# STLink_V3E_SWD.net
KiCad netlist of a schematic drawn in Altium Designer
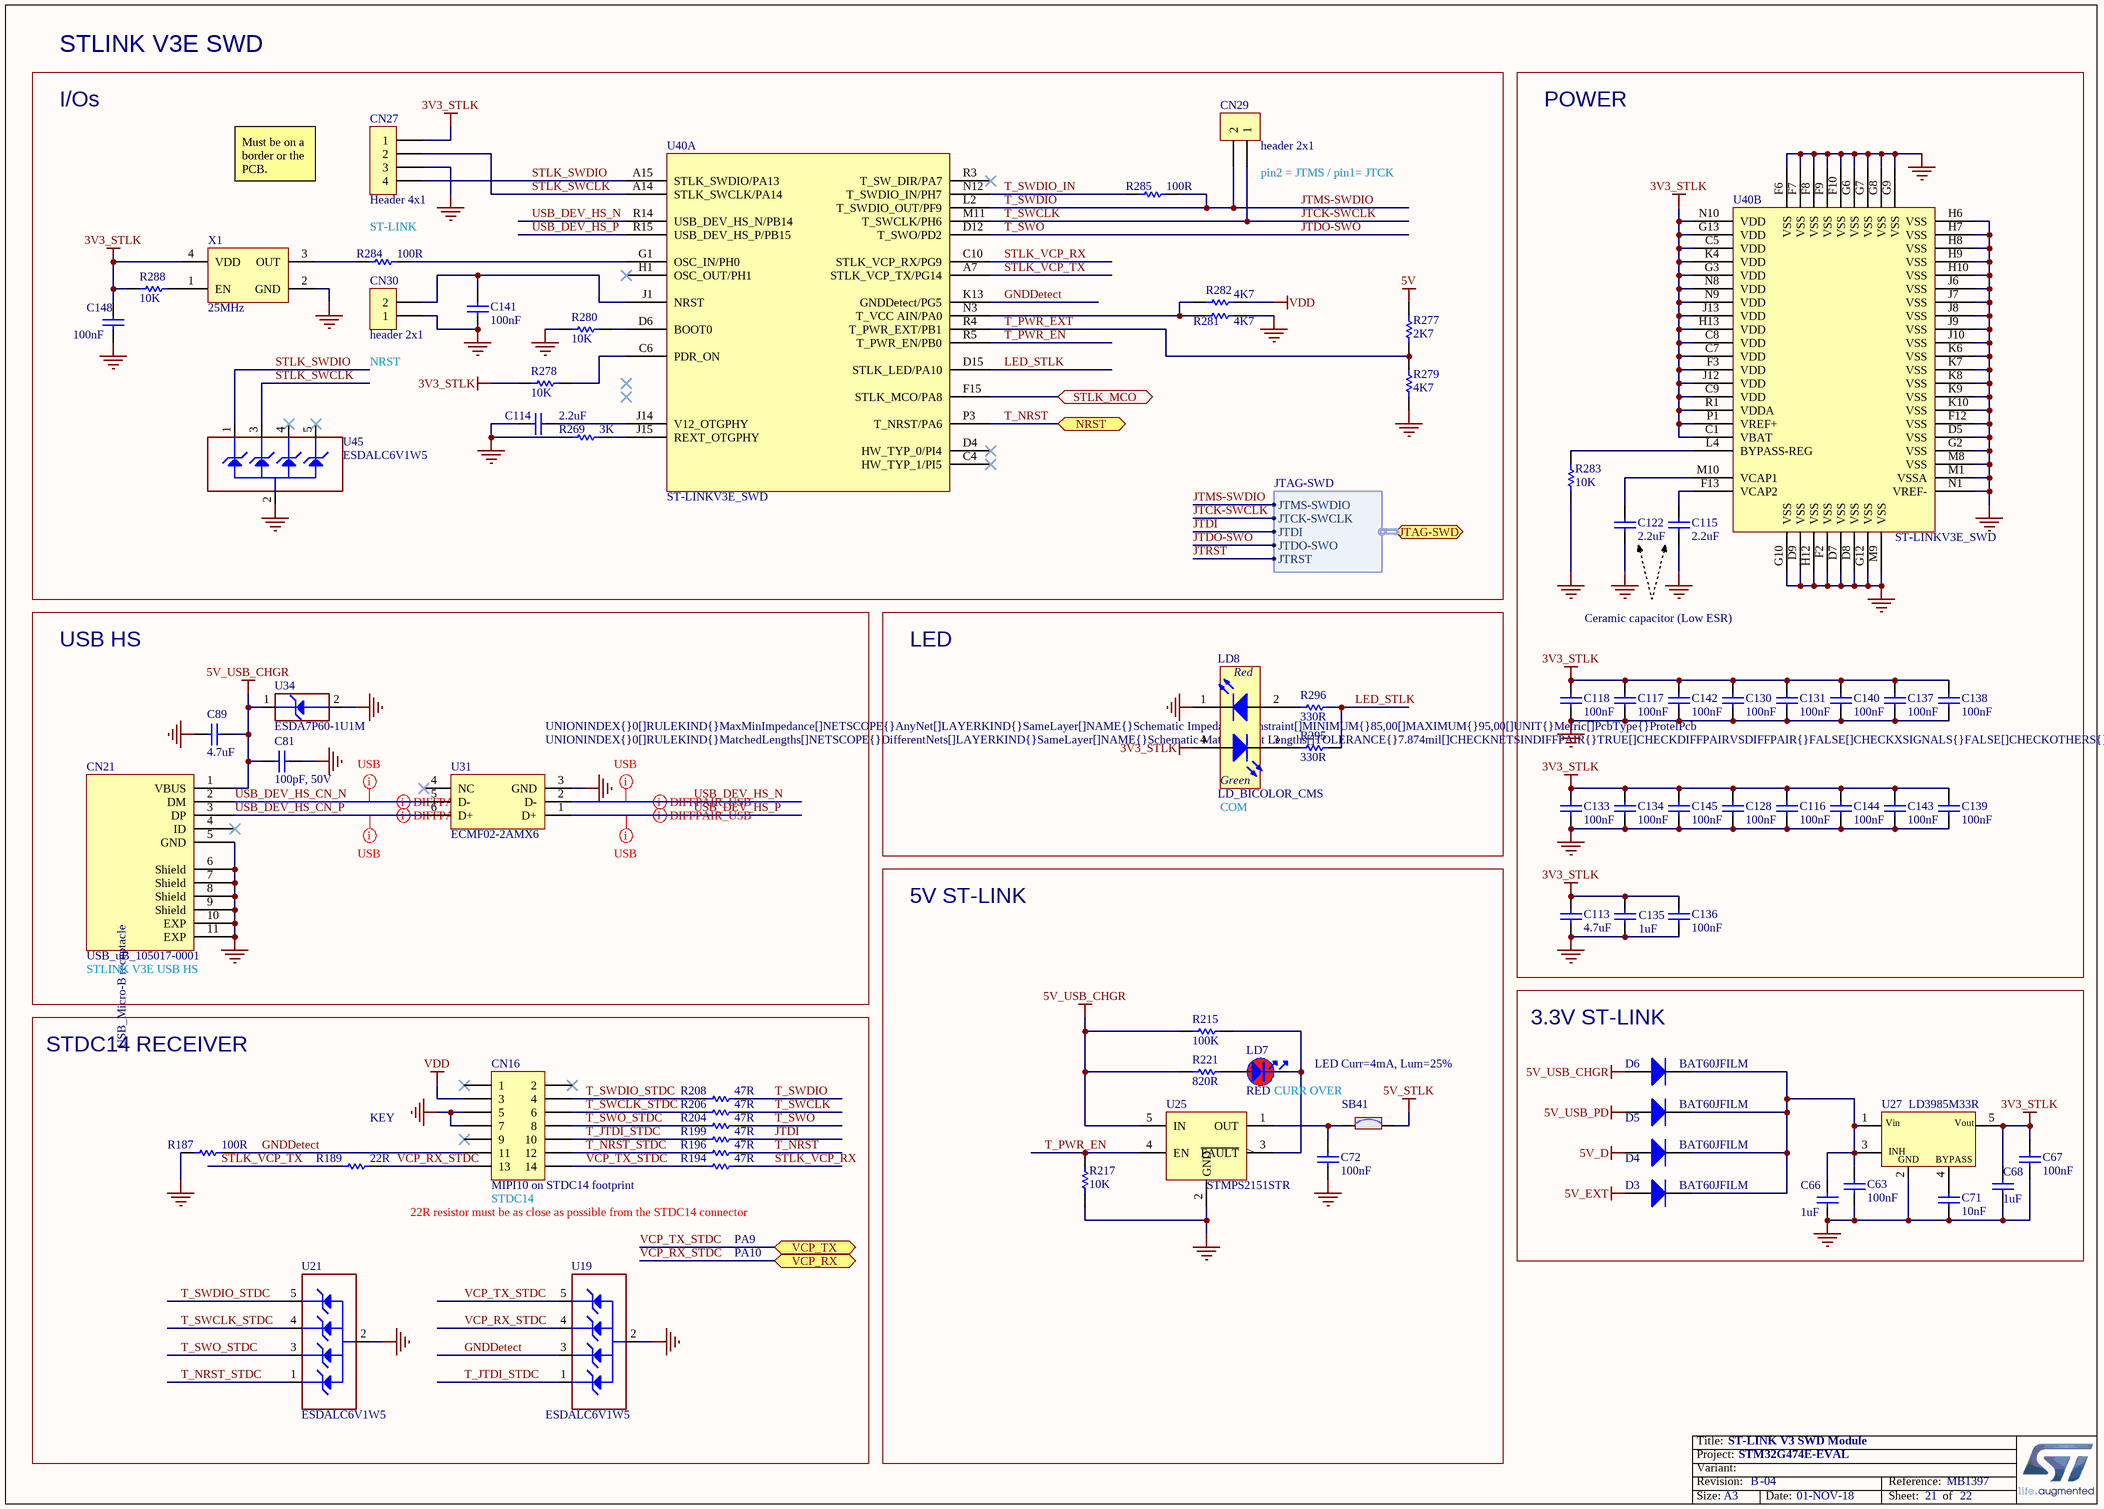
[diagram p0: STLink_V3E_SWD.SchDoc]

(export (version "E")
  (design (tool "Eeschema 10.0.6"))
  (components
    (comp (ref "C63")
      (value "100nF")
      (footprint "C0402")
      (description "Capacitor, MLCC, 100nF, 16V, X7R, 10%, 0402, T=0.5mm")
      (fields
        (field (name "INTERNAL_PART_NUMBER") "MCD-00006")
        (field (name "MANUFACTURER_PART_NUMBER") "CC0402KRX7R7BB104")
      )
      (libsource (lib "MCD_PARTS_database") (part "Capacitor"))
    )
    (comp (ref "C66")
      (value "1uF")
      (footprint "C0603")
      (description "Capacitor, MLCC, 1uF, 16V, X5R, 10%, 0603, T=0,8mm")
      (fields
        (field (name "INTERNAL_PART_NUMBER") "MCD-00010")
        (field (name "MANUFACTURER_PART_NUMBER") "CC0603KRX5R7BB105")
      )
      (libsource (lib "MCD_PARTS_database") (part "Capacitor"))
    )
    (comp (ref "C67")
      (value "100nF")
      (footprint "C0603")
      (description "Capacitor, MLCC, 100nF, 16V, X7R, 10%, 0603, T=0,8mm")
      (fields
        (field (name "INTERNAL_PART_NUMBER") "MCD-00211")
        (field (name "MANUFACTURER_PART_NUMBER") "CC0603KRX7R7BB104")
      )
      (libsource (lib "MCD_PARTS_database") (part "Capacitor"))
    )
    (comp (ref "C68")
      (value "1uF")
      (footprint "C0603")
      (description "Capacitor, MLCC, 1uF, 16V, X5R, 10%, 0603, T=0,8mm")
      (fields
        (field (name "INTERNAL_PART_NUMBER") "MCD-00010")
        (field (name "MANUFACTURER_PART_NUMBER") "CC0603KRX5R7BB105")
      )
      (libsource (lib "MCD_PARTS_database") (part "Capacitor"))
    )
    (comp (ref "C71")
      (value "10nF")
      (footprint "C0402")
      (description "Capacitor, MLCC, 10nF, 16V, X7R, 10%, 0402, T=0.5mm")
      (fields
        (field (name "INTERNAL_PART_NUMBER") "MCD-00011")
        (field (name "MANUFACTURER_PART_NUMBER") "CC0402KRX7R7BB103")
      )
      (libsource (lib "MCD_PARTS_database") (part "Capacitor"))
    )
    (comp (ref "C72")
      (value "100nF")
      (footprint "C0402")
      (description "Capacitor, MLCC, 100nF, 16V, X7R, 10%, 0402, T=0.5mm")
      (fields
        (field (name "INTERNAL_PART_NUMBER") "MCD-00006")
        (field (name "MANUFACTURER_PART_NUMBER") "CC0402KRX7R7BB104")
      )
      (libsource (lib "MCD_PARTS_database") (part "Capacitor"))
    )
    (comp (ref "C81")
      (value "100pF, 50V")
      (footprint "C0603")
      (description "Capacitor,100pF,50V,X7R,10%,0603")
      (fields
        (field (name "INTERNAL_PART_NUMBER") "MCD-01101")
        (field (name "MANUFACTURER_PART_NUMBER") "06035C101JAT4A")
      )
      (libsource (lib "MCD_PARTS_database") (part "Capacitor"))
    )
    (comp (ref "C89")
      (value "4.7uF")
      (footprint "C0603")
      (description "Capacitor, MLCC, 4.7uF, 16V, X5R, 10%, 0603, T=0.8mm")
      (fields
        (field (name "INTERNAL_PART_NUMBER") "MCD-00009")
        (field (name "MANUFACTURER_PART_NUMBER") "CC0603KRX5R7BB475")
      )
      (libsource (lib "MCD_PARTS_database") (part "Capacitor"))
    )
    (comp (ref "C113")
      (value "4.7uF")
      (footprint "C0603")
      (description "Capacitor, MLCC, 4.7uF, 16V, X5R, 10%, 0603, T=0.8mm")
      (fields
        (field (name "INTERNAL_PART_NUMBER") "MCD-00009")
        (field (name "MANUFACTURER_PART_NUMBER") "CC0603KRX5R7BB475")
      )
      (libsource (lib "MCD_PARTS_database") (part "Capacitor"))
    )
    (comp (ref "C114")
      (value "2.2uF")
      (footprint "C0603")
      (description "Capacitor, MLCC, 2.2uF, 10V, X5R, 10%, 0603, T=0,8mm")
      (fields
        (field (name "INTERNAL_PART_NUMBER") "MCD-00012")
        (field (name "MANUFACTURER_PART_NUMBER") "CC0603KRX5R6BB225")
      )
      (libsource (lib "MCD_PARTS_database") (part "Capacitor"))
    )
    (comp (ref "C115")
      (value "2.2uF")
      (footprint "C1206_H1P15")
      (description "Capacitor, MLCC, 2.2uF, 16V, X7R, 10%, 1206, T=1,15mm")
      (fields
        (field (name "INTERNAL_PART_NUMBER") "MCD-00008")
        (field (name "MANUFACTURER_PART_NUMBER") "CC1206KKX7R7BB225")
      )
      (libsource (lib "MCD_PARTS_database") (part "Capacitor"))
    )
    (comp (ref "C116")
      (value "100nF")
      (footprint "C0402")
      (description "Capacitor, MLCC, 100nF, 16V, X7R, 10%, 0402, T=0.5mm")
      (fields
        (field (name "INTERNAL_PART_NUMBER") "MCD-00006")
        (field (name "MANUFACTURER_PART_NUMBER") "CC0402KRX7R7BB104")
      )
      (libsource (lib "MCD_PARTS_database") (part "Capacitor"))
    )
    (comp (ref "C117")
      (value "100nF")
      (footprint "C0402")
      (description "Capacitor, MLCC, 100nF, 16V, X7R, 10%, 0402, T=0.5mm")
      (fields
        (field (name "INTERNAL_PART_NUMBER") "MCD-00006")
        (field (name "MANUFACTURER_PART_NUMBER") "CC0402KRX7R7BB104")
      )
      (libsource (lib "MCD_PARTS_database") (part "Capacitor"))
    )
    (comp (ref "C118")
      (value "100nF")
      (footprint "C0402")
      (description "Capacitor, MLCC, 100nF, 16V, X7R, 10%, 0402, T=0.5mm")
      (fields
        (field (name "INTERNAL_PART_NUMBER") "MCD-00006")
        (field (name "MANUFACTURER_PART_NUMBER") "CC0402KRX7R7BB104")
      )
      (libsource (lib "MCD_PARTS_database") (part "Capacitor"))
    )
    (comp (ref "C122")
      (value "2.2uF")
      (footprint "C1206_H1P15")
      (description "Capacitor, MLCC, 2.2uF, 16V, X7R, 10%, 1206, T=1,15mm")
      (fields
        (field (name "INTERNAL_PART_NUMBER") "MCD-00008")
        (field (name "MANUFACTURER_PART_NUMBER") "CC1206KKX7R7BB225")
      )
      (libsource (lib "MCD_PARTS_database") (part "Capacitor"))
    )
    (comp (ref "C128")
      (value "100nF")
      (footprint "C0402")
      (description "Capacitor, MLCC, 100nF, 16V, X7R, 10%, 0402, T=0.5mm")
      (fields
        (field (name "INTERNAL_PART_NUMBER") "MCD-00006")
        (field (name "MANUFACTURER_PART_NUMBER") "CC0402KRX7R7BB104")
      )
      (libsource (lib "MCD_PARTS_database") (part "Capacitor"))
    )
    (comp (ref "C130")
      (value "100nF")
      (footprint "C0402")
      (description "Capacitor, MLCC, 100nF, 16V, X7R, 10%, 0402, T=0.5mm")
      (fields
        (field (name "INTERNAL_PART_NUMBER") "MCD-00006")
        (field (name "MANUFACTURER_PART_NUMBER") "CC0402KRX7R7BB104")
      )
      (libsource (lib "MCD_PARTS_database") (part "Capacitor"))
    )
    (comp (ref "C131")
      (value "100nF")
      (footprint "C0402")
      (description "Capacitor, MLCC, 100nF, 16V, X7R, 10%, 0402, T=0.5mm")
      (fields
        (field (name "INTERNAL_PART_NUMBER") "MCD-00006")
        (field (name "MANUFACTURER_PART_NUMBER") "CC0402KRX7R7BB104")
      )
      (libsource (lib "MCD_PARTS_database") (part "Capacitor"))
    )
    (comp (ref "C133")
      (value "100nF")
      (footprint "C0402")
      (description "Capacitor, MLCC, 100nF, 16V, X7R, 10%, 0402, T=0.5mm")
      (fields
        (field (name "INTERNAL_PART_NUMBER") "MCD-00006")
        (field (name "MANUFACTURER_PART_NUMBER") "CC0402KRX7R7BB104")
      )
      (libsource (lib "MCD_PARTS_database") (part "Capacitor"))
    )
    (comp (ref "C134")
      (value "100nF")
      (footprint "C0402")
      (description "Capacitor, MLCC, 100nF, 16V, X7R, 10%, 0402, T=0.5mm")
      (fields
        (field (name "INTERNAL_PART_NUMBER") "MCD-00006")
        (field (name "MANUFACTURER_PART_NUMBER") "CC0402KRX7R7BB104")
      )
      (libsource (lib "MCD_PARTS_database") (part "Capacitor"))
    )
    (comp (ref "C135")
      (value "1uF")
      (footprint "C0603")
      (description "Capacitor, MLCC, 1uF, 16V, X5R, 10%, 0603, T=0,8mm")
      (fields
        (field (name "INTERNAL_PART_NUMBER") "MCD-00010")
        (field (name "MANUFACTURER_PART_NUMBER") "CC0603KRX5R7BB105")
      )
      (libsource (lib "MCD_PARTS_database") (part "Capacitor"))
    )
    (comp (ref "C136")
      (value "100nF")
      (footprint "C0402")
      (description "Capacitor, MLCC, 100nF, 16V, X7R, 10%, 0402, T=0.5mm")
      (fields
        (field (name "INTERNAL_PART_NUMBER") "MCD-00006")
        (field (name "MANUFACTURER_PART_NUMBER") "CC0402KRX7R7BB104")
      )
      (libsource (lib "MCD_PARTS_database") (part "Capacitor"))
    )
    (comp (ref "C137")
      (value "100nF")
      (footprint "C0402")
      (description "Capacitor, MLCC, 100nF, 16V, X7R, 10%, 0402, T=0.5mm")
      (fields
        (field (name "INTERNAL_PART_NUMBER") "MCD-00006")
        (field (name "MANUFACTURER_PART_NUMBER") "CC0402KRX7R7BB104")
      )
      (libsource (lib "MCD_PARTS_database") (part "Capacitor"))
    )
    (comp (ref "C138")
      (value "100nF")
      (footprint "C0402")
      (description "Capacitor, MLCC, 100nF, 16V, X7R, 10%, 0402, T=0.5mm")
      (fields
        (field (name "INTERNAL_PART_NUMBER") "MCD-00006")
        (field (name "MANUFACTURER_PART_NUMBER") "CC0402KRX7R7BB104")
      )
      (libsource (lib "MCD_PARTS_database") (part "Capacitor"))
    )
    (comp (ref "C139")
      (value "100nF")
      (footprint "C0402")
      (description "Capacitor, MLCC, 100nF, 16V, X7R, 10%, 0402, T=0.5mm")
      (fields
        (field (name "INTERNAL_PART_NUMBER") "MCD-00006")
        (field (name "MANUFACTURER_PART_NUMBER") "CC0402KRX7R7BB104")
      )
      (libsource (lib "MCD_PARTS_database") (part "Capacitor"))
    )
    (comp (ref "C140")
      (value "100nF")
      (footprint "C0402")
      (description "Capacitor, MLCC, 100nF, 16V, X7R, 10%, 0402, T=0.5mm")
      (fields
        (field (name "INTERNAL_PART_NUMBER") "MCD-00006")
        (field (name "MANUFACTURER_PART_NUMBER") "CC0402KRX7R7BB104")
      )
      (libsource (lib "MCD_PARTS_database") (part "Capacitor"))
    )
    (comp (ref "C141")
      (value "100nF")
      (footprint "C0402")
      (description "Capacitor, MLCC, 100nF, 16V, X7R, 10%, 0402, T=0.5mm")
      (fields
        (field (name "INTERNAL_PART_NUMBER") "MCD-00006")
        (field (name "MANUFACTURER_PART_NUMBER") "CC0402KRX7R7BB104")
      )
      (libsource (lib "MCD_PARTS_database") (part "Capacitor"))
    )
    (comp (ref "C142")
      (value "100nF")
      (footprint "C0402")
      (description "Capacitor, MLCC, 100nF, 16V, X7R, 10%, 0402, T=0.5mm")
      (fields
        (field (name "INTERNAL_PART_NUMBER") "MCD-00006")
        (field (name "MANUFACTURER_PART_NUMBER") "CC0402KRX7R7BB104")
      )
      (libsource (lib "MCD_PARTS_database") (part "Capacitor"))
    )
    (comp (ref "C143")
      (value "100nF")
      (footprint "C0402")
      (description "Capacitor, MLCC, 100nF, 16V, X7R, 10%, 0402, T=0.5mm")
      (fields
        (field (name "INTERNAL_PART_NUMBER") "MCD-00006")
        (field (name "MANUFACTURER_PART_NUMBER") "CC0402KRX7R7BB104")
      )
      (libsource (lib "MCD_PARTS_database") (part "Capacitor"))
    )
    (comp (ref "C144")
      (value "100nF")
      (footprint "C0402")
      (description "Capacitor, MLCC, 100nF, 16V, X7R, 10%, 0402, T=0.5mm")
      (fields
        (field (name "INTERNAL_PART_NUMBER") "MCD-00006")
        (field (name "MANUFACTURER_PART_NUMBER") "CC0402KRX7R7BB104")
      )
      (libsource (lib "MCD_PARTS_database") (part "Capacitor"))
    )
    (comp (ref "C145")
      (value "100nF")
      (footprint "C0402")
      (description "Capacitor, MLCC, 100nF, 16V, X7R, 10%, 0402, T=0.5mm")
      (fields
        (field (name "INTERNAL_PART_NUMBER") "MCD-00006")
        (field (name "MANUFACTURER_PART_NUMBER") "CC0402KRX7R7BB104")
      )
      (libsource (lib "MCD_PARTS_database") (part "Capacitor"))
    )
    (comp (ref "C148")
      (value "100nF")
      (footprint "C0402")
      (description "Capacitor, MLCC, 100nF, 16V, X7R, 10%, 0402, T=0.5mm")
      (fields
        (field (name "INTERNAL_PART_NUMBER") "MCD-00006")
        (field (name "MANUFACTURER_PART_NUMBER") "CC0402KRX7R7BB104")
      )
      (libsource (lib "MCD_PARTS_database") (part "Capacitor"))
    )
    (comp (ref "CN16")
      (value "MIPI10 on STDC14 footprint")
      (footprint "CON_STDC14_Receiver_MEDIUM_WITH_MIPI10_3D")
      (fields
        (field (name "INTERNAL_PART_NUMBER") "MCD-01226")
        (field (name "MANUFACTURER_PART_NUMBER") "FTSH-105-01-L-DV-K")
        (field (name "MANUFACTURER") "SAMTEC")
      )
      (libsource (lib "MCD_PARTS_database") (part "Header 7x2"))
    )
    (comp (ref "CN21")
      (value "USB_uB_105017-0001")
      (footprint "CON_USBMICROB_MOLEX_105017-0001_H2P90")
      (description "USB-MICRO-B, 0.65mm, RA, SMT, Bottom Mount,")
      (fields
        (field (name "INTERNAL_PART_NUMBER") "MCD-00028")
        (field (name "MANUFACTURER_PART_NUMBER") "1050170001")
      )
      (libsource (lib "MCD_PARTS_database") (part "USB_uB_105017.0001"))
    )
    (comp (ref "CN27")
      (value "Header 4x1")
      (footprint "CON_SAMTEC_TSW-104-07-G-S")
      (description "Header, 4x1, 2,54mm, VR, TH, Height 5.84mm/2.54mm")
      (fields
        (field (name "INTERNAL_PART_NUMBER") "MCD-00029")
        (field (name "MANUFACTURER_PART_NUMBER") "TSW-104-07-x-S")
      )
      (libsource (lib "MCD_PARTS_database") (part "Header 4x1"))
    )
    (comp (ref "CN29")
      (value "header 2x1")
      (footprint "CON_988-JIUBABA_PHFS25-11-02-G0B115-T-1")
      (description "Header, 2x1, 2.54mm, VR, TH, Height 6mm/3mm")
      (fields
        (field (name "INTERNAL_PART_NUMBER") "MCD-00314")
        (field (name "MANUFACTURER_PART_NUMBER") "PHFS25-11-02-G0B115-T-1")
      )
      (libsource (lib "MCD_PARTS_database") (part "Header 2x1"))
    )
    (comp (ref "CN30")
      (value "header 2x1")
      (footprint "CON_988-JIUBABA_PHFS25-11-02-G0B115-T-1")
      (description "Header, 2x1, 2.54mm, VR, TH, Height 6mm/3mm")
      (fields
        (field (name "INTERNAL_PART_NUMBER") "MCD-00314")
        (field (name "MANUFACTURER_PART_NUMBER") "PHFS25-11-02-G0B115-T-1")
      )
      (libsource (lib "") (part "Header 2x1_1"))
    )
    (comp (ref "D3")
      (value "BAT60JFILM")
      (footprint "DIO_SOD323")
      (fields
        (field (name "INTERNAL_PART_NUMBER") "MCD-00034")
        (field (name "MANUFACTURER") "STMICROELECTRONICS")
        (field (name "BMS_PART_NUMBER") "9151097")
      )
      (libsource (lib "MCD_PARTS_database") (part "BAT60JFILM"))
    )
    (comp (ref "D4")
      (value "BAT60JFILM")
      (footprint "DIO_SOD323")
      (fields
        (field (name "INTERNAL_PART_NUMBER") "MCD-00034")
        (field (name "MANUFACTURER") "STMICROELECTRONICS")
        (field (name "BMS_PART_NUMBER") "9151097")
      )
      (libsource (lib "MCD_PARTS_database") (part "BAT60JFILM"))
    )
    (comp (ref "D5")
      (value "BAT60JFILM")
      (footprint "DIO_SOD323")
      (fields
        (field (name "INTERNAL_PART_NUMBER") "MCD-00034")
        (field (name "MANUFACTURER") "STMICROELECTRONICS")
        (field (name "BMS_PART_NUMBER") "9151097")
      )
      (libsource (lib "MCD_PARTS_database") (part "BAT60JFILM"))
    )
    (comp (ref "D6")
      (value "BAT60JFILM")
      (footprint "DIO_SOD323")
      (fields
        (field (name "INTERNAL_PART_NUMBER") "MCD-00034")
        (field (name "MANUFACTURER") "STMICROELECTRONICS")
        (field (name "BMS_PART_NUMBER") "9151097")
      )
      (libsource (lib "MCD_PARTS_database") (part "BAT60JFILM"))
    )
    (comp (ref "LD7")
      (value "RED")
      (footprint "LED_0603_VISHAY_VLMS1300-GS08_RED_1A2K_H0P8")
      (description "LED Red, 0603 SMD, 2V Forward Voltage")
      (fields
        (field (name "INTERNAL_PART_NUMBER") "MCD-00587")
        (field (name "MANUFACTURER_PART_NUMBER") "VLMS1300-GS08")
      )
      (libsource (lib "MCD_PARTS_database") (part "LED_red"))
    )
    (comp (ref "LD8")
      (value "LD_BICOLOR_CMS")
      (footprint "LED_BI-GR_HSMF-A201-A00J1")
      (description "LED Bicolor")
      (fields
        (field (name "INTERNAL_PART_NUMBER") "MCD-00051")
        (field (name "MANUFACTURER_PART_NUMBER") "HSMF-A201-A00J1")
      )
      (libsource (lib "MCD_PARTS_database") (part "LD_BICOLOR_CMS"))
    )
    (comp (ref "R187")
      (value "100R")
      (footprint "R0402")
      (description "Resistor,100R,0402,1%,1/16W")
      (fields
        (field (name "INTERNAL_PART_NUMBER") "MCD-00119")
        (field (name "MANUFACTURER_PART_NUMBER") "RC0402FR-07100RL")
      )
      (libsource (lib "MCD_PARTS_database") (part "Resistor"))
    )
    (comp (ref "R189")
      (value "22R")
      (footprint "R0402")
      (description "Resistor,22R,0402,1%,1/16W")
      (fields
        (field (name "INTERNAL_PART_NUMBER") "MCD-00189")
        (field (name "MANUFACTURER_PART_NUMBER") "RC0402FR-0722RL")
      )
      (libsource (lib "MCD_PARTS_database") (part "Resistor"))
    )
    (comp (ref "R194")
      (value "47R")
      (footprint "R0402")
      (description "Resistor,47R,0402,1%,1/16W")
      (fields (field (name "INTERNAL_PART_NUMBER") "MCD-00481") (field (name "Comment") "Resistor"))
      (libsource (lib "MCD_PARTS_database") (part "Resistor"))
    )
    (comp (ref "R196")
      (value "47R")
      (footprint "R0402")
      (description "Resistor,47R,0402,1%,1/16W")
      (fields (field (name "INTERNAL_PART_NUMBER") "MCD-00481") (field (name "Comment") "Resistor"))
      (libsource (lib "MCD_PARTS_database") (part "Resistor"))
    )
    (comp (ref "R199")
      (value "47R")
      (footprint "R0402")
      (description "Resistor,47R,0402,1%,1/16W")
      (fields (field (name "INTERNAL_PART_NUMBER") "MCD-00481") (field (name "Comment") "Resistor"))
      (libsource (lib "MCD_PARTS_database") (part "Resistor"))
    )
    (comp (ref "R204")
      (value "47R")
      (footprint "R0402")
      (description "Resistor,47R,0402,1%,1/16W")
      (fields (field (name "INTERNAL_PART_NUMBER") "MCD-00481") (field (name "Comment") "Resistor"))
      (libsource (lib "MCD_PARTS_database") (part "Resistor"))
    )
    (comp (ref "R206")
      (value "47R")
      (footprint "R0402")
      (description "Resistor,47R,0402,1%,1/16W")
      (fields (field (name "INTERNAL_PART_NUMBER") "MCD-00481") (field (name "Comment") "Resistor"))
      (libsource (lib "MCD_PARTS_database") (part "Resistor"))
    )
    (comp (ref "R208")
      (value "47R")
      (footprint "R0402")
      (description "Resistor,47R,0402,1%,1/16W")
      (fields (field (name "INTERNAL_PART_NUMBER") "MCD-00481") (field (name "Comment") "Resistor"))
      (libsource (lib "MCD_PARTS_database") (part "Resistor"))
    )
    (comp (ref "R215")
      (value "100K")
      (footprint "R0603")
      (description "Resistor,100K,0603,1%,1/10W")
      (fields
        (field (name "INTERNAL_PART_NUMBER") "MCD-00223")
        (field (name "MANUFACTURER_PART_NUMBER") "RC0603FR-07100KL")
      )
      (libsource (lib "MCD_PARTS_database") (part "Resistor"))
    )
    (comp (ref "R217")
      (value "10K")
      (footprint "R0402")
      (description "Resistor,10K,0402,1%,1/16W")
      (fields
        (field (name "INTERNAL_PART_NUMBER") "MCD-00053")
        (field (name "MANUFACTURER_PART_NUMBER") "RC0402FR-0710KL")
      )
      (libsource (lib "MCD_PARTS_database") (part "Resistor"))
    )
    (comp (ref "R221")
      (value "820R")
      (footprint "R0402")
      (description "Resistor,820R,0402,1%,1/16W")
      (fields
        (field (name "INTERNAL_PART_NUMBER") "MCD-00527")
        (field (name "MANUFACTURER_PART_NUMBER") "RC0402FR-07820RL")
      )
      (libsource (lib "MCD_PARTS_database") (part "Resistor"))
    )
    (comp (ref "R269")
      (value "3K")
      (footprint "R0402")
      (description "Resistor,3K,0402,1%,1/16W")
      (fields
        (field (name "INTERNAL_PART_NUMBER") "MCD-00185")
        (field (name "MANUFACTURER_PART_NUMBER") "RC0402FR-073KL")
      )
      (libsource (lib "MCD_PARTS_database") (part "Resistor"))
    )
    (comp (ref "R277")
      (value "2K7")
      (footprint "R0402")
      (description "Resistor,2K7,0402,1%,1/16W")
      (fields
        (field (name "INTERNAL_PART_NUMBER") "MCD-00055")
        (field (name "MANUFACTURER_PART_NUMBER") "RC0402FR-072K7L")
      )
      (libsource (lib "MCD_PARTS_database") (part "Resistor"))
    )
    (comp (ref "R278")
      (value "10K")
      (footprint "R0402")
      (description "Resistor,10K,0402,1%,1/16W")
      (fields
        (field (name "INTERNAL_PART_NUMBER") "MCD-00053")
        (field (name "MANUFACTURER_PART_NUMBER") "RC0402FR-0710KL")
      )
      (libsource (lib "MCD_PARTS_database") (part "Resistor"))
    )
    (comp (ref "R279")
      (value "4K7")
      (footprint "R0402")
      (description "Resistor,4K7,0402,1%,1/16W")
      (fields
        (field (name "INTERNAL_PART_NUMBER") "MCD-00065")
        (field (name "MANUFACTURER_PART_NUMBER") "RC0402FR-074K7L")
      )
      (libsource (lib "MCD_PARTS_database") (part "Resistor"))
    )
    (comp (ref "R280")
      (value "10K")
      (footprint "R0402")
      (description "Resistor,10K,0402,1%,1/16W")
      (fields
        (field (name "INTERNAL_PART_NUMBER") "MCD-00053")
        (field (name "MANUFACTURER_PART_NUMBER") "RC0402FR-0710KL")
      )
      (libsource (lib "MCD_PARTS_database") (part "Resistor"))
    )
    (comp (ref "R281")
      (value "4K7")
      (footprint "R0402")
      (description "Resistor,4K7,0402,1%,1/16W")
      (fields
        (field (name "INTERNAL_PART_NUMBER") "MCD-00065")
        (field (name "MANUFACTURER_PART_NUMBER") "RC0402FR-074K7L")
      )
      (libsource (lib "MCD_PARTS_database") (part "Resistor"))
    )
    (comp (ref "R282")
      (value "4K7")
      (footprint "R0402")
      (description "Resistor,4K7,0402,1%,1/16W")
      (fields
        (field (name "INTERNAL_PART_NUMBER") "MCD-00065")
        (field (name "MANUFACTURER_PART_NUMBER") "RC0402FR-074K7L")
      )
      (libsource (lib "MCD_PARTS_database") (part "Resistor"))
    )
    (comp (ref "R283")
      (value "10K")
      (footprint "R0402")
      (description "Resistor,10K,0402,1%,1/16W")
      (fields
        (field (name "INTERNAL_PART_NUMBER") "MCD-00053")
        (field (name "MANUFACTURER_PART_NUMBER") "RC0402FR-0710KL")
      )
      (libsource (lib "MCD_PARTS_database") (part "Resistor"))
    )
    (comp (ref "R284")
      (value "100R")
      (footprint "R0402")
      (description "Resistor,100R,0402,1%,1/16W")
      (fields
        (field (name "INTERNAL_PART_NUMBER") "MCD-00119")
        (field (name "MANUFACTURER_PART_NUMBER") "RC0402FR-07100RL")
      )
      (libsource (lib "MCD_PARTS_database") (part "Resistor"))
    )
    (comp (ref "R285")
      (value "100R")
      (footprint "R0402")
      (description "Resistor,100R,0402,1%,1/16W")
      (fields
        (field (name "INTERNAL_PART_NUMBER") "MCD-00119")
        (field (name "MANUFACTURER_PART_NUMBER") "RC0402FR-07100RL")
      )
      (libsource (lib "MCD_PARTS_database") (part "Resistor"))
    )
    (comp (ref "R288")
      (value "10K")
      (footprint "R0402")
      (description "Resistor,10K,0402,1%,1/16W")
      (fields
        (field (name "INTERNAL_PART_NUMBER") "MCD-00053")
        (field (name "MANUFACTURER_PART_NUMBER") "RC0402FR-0710KL")
      )
      (libsource (lib "MCD_PARTS_database") (part "Resistor"))
    )
    (comp (ref "R295")
      (value "330R")
      (footprint "R0603")
      (description "Resistor,330R,0603,1%,1/10W")
      (fields
        (field (name "INTERNAL_PART_NUMBER") "MCD-00197")
        (field (name "MANUFACTURER_PART_NUMBER") "RC0603FR-07330RL")
      )
      (libsource (lib "MCD_PARTS_database") (part "Resistor"))
    )
    (comp (ref "R296")
      (value "330R")
      (footprint "R0603")
      (description "Resistor,330R,0603,1%,1/10W")
      (fields
        (field (name "INTERNAL_PART_NUMBER") "MCD-00197")
        (field (name "MANUFACTURER_PART_NUMBER") "RC0603FR-07330RL")
      )
      (libsource (lib "MCD_PARTS_database") (part "Resistor"))
    )
    (comp (ref "SB41")
      (value "SB_ON")
      (footprint "SOLDER-BRIDGE_R0603-0R")
      (description "Solder Bridge ON")
      (fields
        (field (name "INTERNAL_PART_NUMBER") "MCD-00071")
        (field (name "MANUFACTURER_PART_NUMBER") "RC0603JR-070RL")
      )
      (libsource (lib "MCD_PARTS_database") (part "SB_ON"))
    )
    (comp (ref "U19")
      (value "ESDALC6V1W5")
      (footprint "ESD_SOT323-5L")
      (description "Dual Transil array for ESD protection")
      (fields
        (field (name "INTERNAL_PART_NUMBER") "MCD-00136")
        (field (name "MANUFACTURER") "STMICROELECTRONICS")
      )
      (libsource (lib "MCD_PARTS_database") (part "ESDALC6V1W5"))
    )
    (comp (ref "U21")
      (value "ESDALC6V1W5")
      (footprint "ESD_SOT323-5L")
      (description "Dual Transil array for ESD protection")
      (fields
        (field (name "INTERNAL_PART_NUMBER") "MCD-00136")
        (field (name "MANUFACTURER") "STMICROELECTRONICS")
      )
      (libsource (lib "MCD_PARTS_database") (part "ESDALC6V1W5"))
    )
    (comp (ref "U25")
      (value "STMPS2151STR")
      (footprint "MOS_SOT23-5L")
      (description "500mA, Enhanced single channel power switches with active high enable pin")
      (fields
        (field (name "INTERNAL_PART_NUMBER") "MCD-00159")
        (field (name "MANUFACTURER") "STMICROELECTRONICS")
      )
      (libsource (lib "MCD_PARTS_database") (part "STMPS2151STR"))
    )
    (comp (ref "U27")
      (value "LD3985M33R")
      (footprint "REG_SOT23-5L")
      (description "Ultra low drop-low noise BiCMOS voltage, regulators low ESR capacitors compatible")
      (fields
        (field (name "INTERNAL_PART_NUMBER") "MCD-00086")
        (field (name "MANUFACTURER") "STMICROELECTRONICS")
      )
      (libsource (lib "MCD_PARTS_database") (part "LD3985M33R"))
    )
    (comp (ref "U31")
      (value "ECMF02-2AMX6")
      (footprint "ESD_QFN-6L_1P7X1P5_P050")
      (description "Common mode filter with ESD protection for USB 2.0 interface")
      (fields
        (field (name "INTERNAL_PART_NUMBER") "MCD-00649")
        (field (name "MANUFACTURER") "STMICROELECTRONICS")
      )
      (libsource (lib "MCD_PARTS_database") (part "ECMF02-2AMX6"))
    )
    (comp (ref "U34")
      (value "ESDA7P60-1U1M")
      (footprint "ESD_QFN2_1P6X1_P125")
      (description "High power transient voltage suppressor, 7V breakdown")
      (fields
        (field (name "INTERNAL_PART_NUMBER") "MCD-00251")
        (field (name "MANUFACTURER") "STMICROELECTRONICS")
      )
      (libsource (lib "MCD_PARTS_database") (part "ESD-TRANSIL"))
    )
    (comp (ref "U40")
      (value "ST-LINKV3E_SWD")
      (footprint "ICC_UFBGA201_176+25_10X10_P065")
      (description "STM32F723IEK  (STM32F7) BGA176")
      (fields
        (field (name "INTERNAL_PART_NUMBER") "MCD-00596")
        (field (name "MANUFACTURER_PART_NUMBER") "STM32F723IEK6")
      )
      (libsource (lib "MCD_PARTS_database") (part "ST-LINKV3E_SWD"))
    )
    (comp (ref "U45")
      (value "ESDALC6V1W5")
      (footprint "ESD_SOT323-5L")
      (description "Dual Transil array for ESD protection")
      (fields
        (field (name "INTERNAL_PART_NUMBER") "MCD-00136")
        (field (name "MANUFACTURER") "STMICROELECTRONICS")
      )
      (libsource (lib "MCD_PARTS_database") (part "ESDALC6V1W5"))
    )
    (comp (ref "X1")
      (value "25MHz")
      (footprint "OSC_NDK_NZ2520SB_4P")
      (description "Oscillator 25.00Mhz, -+50PPM, 3.3V, Temp -55 to +125°C")
      (fields
        (field (name "INTERNAL_PART_NUMBER") "MCD-00597")
        (field (name "MANUFACTURER_PART_NUMBER") "NZ2520SB 25MHz END4869B")
      )
      (libsource (lib "MCD_PARTS_database") (part "OSCILLATOR_4_PINS"))
    )
  )
  (nets
    (net (code "2") (name "/GNDDetect") (class "Default")
      (node (ref "CN16") (pin "11") (pinfunction "11_11") (pintype "passive"))
      (node (ref "R187") (pin "2") (pinfunction "2_2") (pintype "passive"))
      (node (ref "U19") (pin "3") (pinfunction "IO2_3") (pintype "passive"))
      (node (ref "U40") (pin "K13") (pinfunction "GNDDetect/PG5_K13") (pintype "passive"))
    )
    (net (code "3") (name "/JTCK-SWCLK") (class "Default")
      (node (ref "CN29") (pin "1") (pinfunction "1_1") (pintype "passive"))
      (node (ref "R206") (pin "2") (pinfunction "2_2") (pintype "passive"))
      (node (ref "U40") (pin "M11") (pinfunction "T_SWCLK/PH6_M11") (pintype "passive"))
    )
    (net (code "4") (name "/JTDI") (class "Default")
      (node (ref "R199") (pin "2") (pinfunction "2_2") (pintype "passive"))
    )
    (net (code "5") (name "/JTDO-SWO") (class "Default")
      (node (ref "R204") (pin "2") (pinfunction "2_2") (pintype "passive"))
      (node (ref "U40") (pin "D12") (pinfunction "T_SWO/PD2_D12") (pintype "passive"))
    )
    (net (code "6") (name "/JTMS-SWDIO") (class "Default")
      (node (ref "CN29") (pin "2") (pinfunction "2_2") (pintype "passive"))
      (node (ref "R208") (pin "2") (pinfunction "2_2") (pintype "passive"))
      (node (ref "R285") (pin "2") (pinfunction "2_2") (pintype "passive"))
      (node (ref "U40") (pin "L2") (pinfunction "T_SWDIO_OUT/PF9_L2") (pintype "passive"))
    )
    (net (code "8") (name "/LED_STLK") (class "Default")
      (node (ref "R295") (pin "2") (pinfunction "2_2") (pintype "passive"))
      (node (ref "R296") (pin "2") (pinfunction "2_2") (pintype "passive"))
      (node (ref "U40") (pin "D15") (pinfunction "STLK_LED/PA10_D15") (pintype "passive"))
    )
    (net (code "9") (name "/STLK_MCO") (class "Default")
      (node (ref "U40") (pin "F15") (pinfunction "STLK_MCO/PA8_F15") (pintype "passive"))
    )
    (net (code "10") (name "/STLK_SWCLK") (class "Default")
      (node (ref "CN27") (pin "2") (pinfunction "2_2") (pintype "passive"))
      (node (ref "U40") (pin "A14") (pinfunction "STLK_SWCLK/PA14_A14") (pintype "passive"))
      (node (ref "U45") (pin "3") (pinfunction "IO2_3") (pintype "passive"))
    )
    (net (code "11") (name "/STLK_SWDIO") (class "Default")
      (node (ref "CN27") (pin "4") (pinfunction "4_4") (pintype "passive"))
      (node (ref "U40") (pin "A15") (pinfunction "STLK_SWDIO/PA13_A15") (pintype "passive"))
      (node (ref "U45") (pin "1") (pinfunction "IO1_1") (pintype "passive"))
    )
    (net (code "12") (name "/STLK_VCP_RX") (class "Default")
      (node (ref "R194") (pin "2") (pinfunction "2_2") (pintype "passive"))
      (node (ref "U40") (pin "C10") (pinfunction "STLK_VCP_RX/PG9_C10") (pintype "passive"))
    )
    (net (code "13") (name "/STLK_VCP_TX") (class "Default")
      (node (ref "R189") (pin "1") (pinfunction "1_1") (pintype "passive"))
      (node (ref "U40") (pin "A7") (pinfunction "STLK_VCP_TX/PG14_A7") (pintype "passive"))
    )
    (net (code "14") (name "/T_JTDI_STDC") (class "Default")
      (node (ref "CN16") (pin "10") (pinfunction "10_10") (pintype "passive"))
      (node (ref "R199") (pin "1") (pinfunction "1_1") (pintype "passive"))
      (node (ref "U19") (pin "1") (pinfunction "IO1_1") (pintype "passive"))
    )
    (net (code "15") (name "/T_NRST") (class "Default")
      (node (ref "R196") (pin "2") (pinfunction "2_2") (pintype "passive"))
      (node (ref "U40") (pin "P3") (pinfunction "T_NRST/PA6_P3") (pintype "passive"))
    )
    (net (code "16") (name "/T_NRST_STDC") (class "Default")
      (node (ref "CN16") (pin "12") (pinfunction "12_12") (pintype "passive"))
      (node (ref "R196") (pin "1") (pinfunction "1_1") (pintype "passive"))
      (node (ref "U21") (pin "1") (pinfunction "IO1_1") (pintype "passive"))
    )
    (net (code "17") (name "/T_PWR_EN") (class "Default")
      (node (ref "R217") (pin "2") (pinfunction "2_2") (pintype "passive"))
      (node (ref "U25") (pin "4") (pinfunction "EN_4") (pintype "passive"))
      (node (ref "U40") (pin "R5") (pinfunction "T_PWR_EN/PB0_R5") (pintype "passive"))
    )
    (net (code "18") (name "/T_PWR_EXT") (class "Default")
      (node (ref "R277") (pin "1") (pinfunction "1_1") (pintype "passive"))
      (node (ref "R279") (pin "2") (pinfunction "2_2") (pintype "passive"))
      (node (ref "U40") (pin "R4") (pinfunction "T_PWR_EXT/PB1_R4") (pintype "passive"))
    )
    (net (code "19") (name "/T_SWCLK_STDC") (class "Default")
      (node (ref "CN16") (pin "6") (pinfunction "6_6") (pintype "passive"))
      (node (ref "R206") (pin "1") (pinfunction "1_1") (pintype "passive"))
      (node (ref "U21") (pin "4") (pinfunction "IO3_4") (pintype "passive"))
    )
    (net (code "20") (name "/T_SWDIO_IN") (class "Default")
      (node (ref "R285") (pin "1") (pinfunction "1_1") (pintype "passive"))
      (node (ref "U40") (pin "N12") (pinfunction "T_SWDIO_IN/PH7_N12") (pintype "passive"))
    )
    (net (code "21") (name "/T_SWDIO_STDC") (class "Default")
      (node (ref "CN16") (pin "4") (pinfunction "4_4") (pintype "passive"))
      (node (ref "R208") (pin "1") (pinfunction "1_1") (pintype "passive"))
      (node (ref "U21") (pin "5") (pinfunction "IO4_5") (pintype "passive"))
    )
    (net (code "22") (name "/T_SWO_STDC") (class "Default")
      (node (ref "CN16") (pin "8") (pinfunction "8_8") (pintype "passive"))
      (node (ref "R204") (pin "1") (pinfunction "1_1") (pintype "passive"))
      (node (ref "U21") (pin "3") (pinfunction "IO2_3") (pintype "passive"))
    )
    (net (code "23") (name "/USB_DEV_HS_CN_N") (class "Default")
      (node (ref "CN21") (pin "2") (pinfunction "DM_2") (pintype "passive"))
      (node (ref "U31") (pin "5") (pinfunction "D-_5") (pintype "passive"))
    )
    (net (code "24") (name "/USB_DEV_HS_CN_P") (class "Default")
      (node (ref "CN21") (pin "3") (pinfunction "DP_3") (pintype "passive"))
      (node (ref "U31") (pin "6") (pinfunction "D+_6") (pintype "passive"))
    )
    (net (code "25") (name "/USB_DEV_HS_N") (class "Default")
      (node (ref "U31") (pin "2") (pinfunction "D-_2") (pintype "passive"))
      (node (ref "U40") (pin "R14") (pinfunction "USB_DEV_HS_N/PB14_R14") (pintype "passive"))
    )
    (net (code "26") (name "/USB_DEV_HS_P") (class "Default")
      (node (ref "U31") (pin "1") (pinfunction "D+_1") (pintype "passive"))
      (node (ref "U40") (pin "R15") (pinfunction "USB_DEV_HS_P/PB15_R15") (pintype "passive"))
    )
    (net (code "27") (name "/VCP_RX_STDC") (class "Default")
      (node (ref "CN16") (pin "13") (pinfunction "13_13") (pintype "passive"))
      (node (ref "R189") (pin "2") (pinfunction "2_2") (pintype "passive"))
      (node (ref "U19") (pin "4") (pinfunction "IO3_4") (pintype "passive"))
    )
    (net (code "28") (name "/VCP_TX_STDC") (class "Default")
      (node (ref "CN16") (pin "14") (pinfunction "14_14") (pintype "passive"))
      (node (ref "R194") (pin "1") (pinfunction "1_1") (pintype "passive"))
      (node (ref "U19") (pin "5") (pinfunction "IO4_5") (pintype "passive"))
    )
    (net (code "30") (name "3V3_STLK") (class "Default")
      (node (ref "C113") (pin "2") (pinfunction "2_2") (pintype "passive"))
      (node (ref "C116") (pin "2") (pinfunction "2_2") (pintype "passive"))
      (node (ref "C117") (pin "2") (pinfunction "2_2") (pintype "passive"))
      (node (ref "C118") (pin "2") (pinfunction "2_2") (pintype "passive"))
      (node (ref "C128") (pin "2") (pinfunction "2_2") (pintype "passive"))
      (node (ref "C130") (pin "2") (pinfunction "2_2") (pintype "passive"))
      (node (ref "C131") (pin "2") (pinfunction "2_2") (pintype "passive"))
      (node (ref "C133") (pin "2") (pinfunction "2_2") (pintype "passive"))
      (node (ref "C134") (pin "2") (pinfunction "2_2") (pintype "passive"))
      (node (ref "C135") (pin "2") (pinfunction "2_2") (pintype "passive"))
      (node (ref "C136") (pin "2") (pinfunction "2_2") (pintype "passive"))
      (node (ref "C137") (pin "2") (pinfunction "2_2") (pintype "passive"))
      (node (ref "C138") (pin "2") (pinfunction "2_2") (pintype "passive"))
      (node (ref "C139") (pin "2") (pinfunction "2_2") (pintype "passive"))
      (node (ref "C140") (pin "2") (pinfunction "2_2") (pintype "passive"))
      (node (ref "C142") (pin "2") (pinfunction "2_2") (pintype "passive"))
      (node (ref "C143") (pin "2") (pinfunction "2_2") (pintype "passive"))
      (node (ref "C144") (pin "2") (pinfunction "2_2") (pintype "passive"))
      (node (ref "C145") (pin "2") (pinfunction "2_2") (pintype "passive"))
      (node (ref "C148") (pin "2") (pinfunction "2_2") (pintype "passive"))
      (node (ref "C67") (pin "2") (pinfunction "2_2") (pintype "passive"))
      (node (ref "C68") (pin "2") (pinfunction "2_2") (pintype "passive"))
      (node (ref "CN27") (pin "1") (pinfunction "1_1") (pintype "passive"))
      (node (ref "LD8") (pin "4") (pinfunction "YellowGreen_anode_4") (pintype "passive"))
      (node (ref "R278") (pin "1") (pinfunction "1_1") (pintype "passive"))
      (node (ref "R288") (pin "1") (pinfunction "1_1") (pintype "passive"))
      (node (ref "U27") (pin "5") (pinfunction "Vout_5") (pintype "passive"))
      (node (ref "U40") (pin "C1") (pinfunction "VBAT_C1") (pintype "passive"))
      (node (ref "U40") (pin "C5") (pinfunction "VDD_C5") (pintype "passive"))
      (node (ref "U40") (pin "C7") (pinfunction "VDD_C7") (pintype "passive"))
      (node (ref "U40") (pin "C8") (pinfunction "VDD_C8") (pintype "passive"))
      (node (ref "U40") (pin "C9") (pinfunction "VDD_C9") (pintype "passive"))
      (node (ref "U40") (pin "F3") (pinfunction "VDD_F3") (pintype "passive"))
      (node (ref "U40") (pin "G13") (pinfunction "VDD_G13") (pintype "passive"))
      (node (ref "U40") (pin "G3") (pinfunction "VDD_G3") (pintype "passive"))
      (node (ref "U40") (pin "H13") (pinfunction "VDD_H13") (pintype "passive"))
      (node (ref "U40") (pin "J12") (pinfunction "VDD_J12") (pintype "passive"))
      (node (ref "U40") (pin "J13") (pinfunction "VDD_J13") (pintype "passive"))
      (node (ref "U40") (pin "K4") (pinfunction "VDD_K4") (pintype "passive"))
      (node (ref "U40") (pin "N10") (pinfunction "VDD_N10") (pintype "passive"))
      (node (ref "U40") (pin "N8") (pinfunction "VDD_N8") (pintype "passive"))
      (node (ref "U40") (pin "N9") (pinfunction "VDD_N9") (pintype "passive"))
      (node (ref "U40") (pin "P1") (pinfunction "VREF+_P1") (pintype "passive"))
      (node (ref "U40") (pin "R1") (pinfunction "VDDA_R1") (pintype "passive"))
      (node (ref "X1") (pin "4") (pinfunction "VDD_4") (pintype "passive"))
    )
    (net (code "31") (name "5V") (class "Default")
      (node (ref "R277") (pin "2") (pinfunction "2_2") (pintype "passive"))
    )
    (net (code "32") (name "5V_D") (class "Default")
      (node (ref "D4") (pin "1") (pinfunction "A_1") (pintype "passive"))
    )
    (net (code "33") (name "5V_EXT") (class "Default")
      (node (ref "D3") (pin "1") (pinfunction "A_1") (pintype "passive"))
    )
    (net (code "34") (name "5V_STLK") (class "Default")
      (node (ref "SB41") (pin "2") (pinfunction "2_2") (pintype "passive"))
    )
    (net (code "35") (name "5V_USB_CHGR") (class "Default")
      (node (ref "C81") (pin "1") (pinfunction "1_1") (pintype "passive"))
      (node (ref "C89") (pin "2") (pinfunction "2_2") (pintype "passive"))
      (node (ref "CN21") (pin "1") (pinfunction "VBUS_1") (pintype "passive"))
      (node (ref "D6") (pin "1") (pinfunction "A_1") (pintype "passive"))
      (node (ref "R215") (pin "1") (pinfunction "1_1") (pintype "passive"))
      (node (ref "R221") (pin "1") (pinfunction "1_1") (pintype "passive"))
      (node (ref "U25") (pin "5") (pinfunction "IN_5") (pintype "passive"))
      (node (ref "U34") (pin "1") (pinfunction "IO1_1") (pintype "passive"))
    )
    (net (code "36") (name "5V_USB_PD") (class "Default")
      (node (ref "D5") (pin "1") (pinfunction "A_1") (pintype "passive"))
    )
    (net (code "37") (name "GND") (class "Default")
      (node (ref "C113") (pin "1") (pinfunction "1_1") (pintype "passive"))
      (node (ref "C114") (pin "1") (pinfunction "1_1") (pintype "passive"))
      (node (ref "C115") (pin "1") (pinfunction "1_1") (pintype "passive"))
      (node (ref "C116") (pin "1") (pinfunction "1_1") (pintype "passive"))
      (node (ref "C117") (pin "1") (pinfunction "1_1") (pintype "passive"))
      (node (ref "C118") (pin "1") (pinfunction "1_1") (pintype "passive"))
      (node (ref "C122") (pin "1") (pinfunction "1_1") (pintype "passive"))
      (node (ref "C128") (pin "1") (pinfunction "1_1") (pintype "passive"))
      (node (ref "C130") (pin "1") (pinfunction "1_1") (pintype "passive"))
      (node (ref "C131") (pin "1") (pinfunction "1_1") (pintype "passive"))
      (node (ref "C133") (pin "1") (pinfunction "1_1") (pintype "passive"))
      (node (ref "C134") (pin "1") (pinfunction "1_1") (pintype "passive"))
      (node (ref "C135") (pin "1") (pinfunction "1_1") (pintype "passive"))
      (node (ref "C136") (pin "1") (pinfunction "1_1") (pintype "passive"))
      (node (ref "C137") (pin "1") (pinfunction "1_1") (pintype "passive"))
      (node (ref "C138") (pin "1") (pinfunction "1_1") (pintype "passive"))
      (node (ref "C139") (pin "1") (pinfunction "1_1") (pintype "passive"))
      (node (ref "C140") (pin "1") (pinfunction "1_1") (pintype "passive"))
      (node (ref "C141") (pin "1") (pinfunction "1_1") (pintype "passive"))
      (node (ref "C142") (pin "1") (pinfunction "1_1") (pintype "passive"))
      (node (ref "C143") (pin "1") (pinfunction "1_1") (pintype "passive"))
      (node (ref "C144") (pin "1") (pinfunction "1_1") (pintype "passive"))
      (node (ref "C145") (pin "1") (pinfunction "1_1") (pintype "passive"))
      (node (ref "C148") (pin "1") (pinfunction "1_1") (pintype "passive"))
      (node (ref "C63") (pin "1") (pinfunction "1_1") (pintype "passive"))
      (node (ref "C66") (pin "2") (pinfunction "2_2") (pintype "passive"))
      (node (ref "C67") (pin "1") (pinfunction "1_1") (pintype "passive"))
      (node (ref "C68") (pin "1") (pinfunction "1_1") (pintype "passive"))
      (node (ref "C71") (pin "1") (pinfunction "1_1") (pintype "passive"))
      (node (ref "C72") (pin "1") (pinfunction "1_1") (pintype "passive"))
      (node (ref "C81") (pin "2") (pinfunction "2_2") (pintype "passive"))
      (node (ref "C89") (pin "1") (pinfunction "1_1") (pintype "passive"))
      (node (ref "CN16") (pin "5") (pinfunction "5_5") (pintype "passive"))
      (node (ref "CN16") (pin "7") (pinfunction "7_7") (pintype "passive"))
      (node (ref "CN21") (pin "10") (pinfunction "EXP_10") (pintype "passive"))
      (node (ref "CN21") (pin "11") (pinfunction "EXP_11") (pintype "passive"))
      (node (ref "CN21") (pin "5") (pinfunction "GND_5") (pintype "passive"))
      (node (ref "CN21") (pin "6") (pinfunction "Shield_6") (pintype "passive"))
      (node (ref "CN21") (pin "7") (pinfunction "Shield_7") (pintype "passive"))
      (node (ref "CN21") (pin "8") (pinfunction "Shield_8") (pintype "passive"))
      (node (ref "CN21") (pin "9") (pinfunction "Shield_9") (pintype "passive"))
      (node (ref "CN27") (pin "3") (pinfunction "3_3") (pintype "passive"))
      (node (ref "CN30") (pin "1") (pinfunction "1_1") (pintype "passive"))
      (node (ref "LD8") (pin "1") (pinfunction "RED_cathode_1") (pintype "passive"))
      (node (ref "R187") (pin "1") (pinfunction "1_1") (pintype "passive"))
      (node (ref "R217") (pin "1") (pinfunction "1_1") (pintype "passive"))
      (node (ref "R269") (pin "1") (pinfunction "1_1") (pintype "passive"))
      (node (ref "R279") (pin "1") (pinfunction "1_1") (pintype "passive"))
      (node (ref "R280") (pin "1") (pinfunction "1_1") (pintype "passive"))
      (node (ref "R281") (pin "2") (pinfunction "2_2") (pintype "passive"))
      (node (ref "R283") (pin "1") (pinfunction "1_1") (pintype "passive"))
      (node (ref "U19") (pin "2") (pinfunction "GND_2") (pintype "passive"))
      (node (ref "U21") (pin "2") (pinfunction "GND_2") (pintype "passive"))
      (node (ref "U25") (pin "2") (pinfunction "GND_2") (pintype "passive"))
      (node (ref "U27") (pin "2") (pinfunction "GND_2") (pintype "passive"))
      (node (ref "U31") (pin "3") (pinfunction "GND_3") (pintype "passive"))
      (node (ref "U34") (pin "2") (pinfunction "GND_2") (pintype "passive"))
      (node (ref "U40") (pin "D5") (pinfunction "VSS_D5") (pintype "passive"))
      (node (ref "U40") (pin "D7") (pinfunction "VSS_D7") (pintype "passive"))
      (node (ref "U40") (pin "D8") (pinfunction "VSS_D8") (pintype "passive"))
      (node (ref "U40") (pin "D9") (pinfunction "VSS_D9") (pintype "passive"))
      (node (ref "U40") (pin "F10") (pinfunction "VSS_F10") (pintype "passive"))
      (node (ref "U40") (pin "F12") (pinfunction "VSS_F12") (pintype "passive"))
      (node (ref "U40") (pin "F2") (pinfunction "VSS_F2") (pintype "passive"))
      (node (ref "U40") (pin "F6") (pinfunction "VSS_F6") (pintype "passive"))
      (node (ref "U40") (pin "F7") (pinfunction "VSS_F7") (pintype "passive"))
      (node (ref "U40") (pin "F8") (pinfunction "VSS_F8") (pintype "passive"))
      (node (ref "U40") (pin "F9") (pinfunction "VSS_F9") (pintype "passive"))
      (node (ref "U40") (pin "G10") (pinfunction "VSS_G10") (pintype "passive"))
      (node (ref "U40") (pin "G12") (pinfunction "VSS_G12") (pintype "passive"))
      (node (ref "U40") (pin "G2") (pinfunction "VSS_G2") (pintype "passive"))
      (node (ref "U40") (pin "G6") (pinfunction "VSS_G6") (pintype "passive"))
      (node (ref "U40") (pin "G7") (pinfunction "VSS_G7") (pintype "passive"))
      (node (ref "U40") (pin "G8") (pinfunction "VSS_G8") (pintype "passive"))
      (node (ref "U40") (pin "G9") (pinfunction "VSS_G9") (pintype "passive"))
      (node (ref "U40") (pin "H10") (pinfunction "VSS_H10") (pintype "passive"))
      (node (ref "U40") (pin "H12") (pinfunction "VSS_H12") (pintype "passive"))
      (node (ref "U40") (pin "H6") (pinfunction "VSS_H6") (pintype "passive"))
      (node (ref "U40") (pin "H7") (pinfunction "VSS_H7") (pintype "passive"))
      (node (ref "U40") (pin "H8") (pinfunction "VSS_H8") (pintype "passive"))
      (node (ref "U40") (pin "H9") (pinfunction "VSS_H9") (pintype "passive"))
      (node (ref "U40") (pin "J10") (pinfunction "VSS_J10") (pintype "passive"))
      (node (ref "U40") (pin "J6") (pinfunction "VSS_J6") (pintype "passive"))
      (node (ref "U40") (pin "J7") (pinfunction "VSS_J7") (pintype "passive"))
      (node (ref "U40") (pin "J8") (pinfunction "VSS_J8") (pintype "passive"))
      (node (ref "U40") (pin "J9") (pinfunction "VSS_J9") (pintype "passive"))
      (node (ref "U40") (pin "K10") (pinfunction "VSS_K10") (pintype "passive"))
      (node (ref "U40") (pin "K6") (pinfunction "VSS_K6") (pintype "passive"))
      (node (ref "U40") (pin "K7") (pinfunction "VSS_K7") (pintype "passive"))
      (node (ref "U40") (pin "K8") (pinfunction "VSS_K8") (pintype "passive"))
      (node (ref "U40") (pin "K9") (pinfunction "VSS_K9") (pintype "passive"))
      (node (ref "U40") (pin "M1") (pinfunction "VSSA_M1") (pintype "passive"))
      (node (ref "U40") (pin "M8") (pinfunction "VSS_M8") (pintype "passive"))
      (node (ref "U40") (pin "M9") (pinfunction "VSS_M9") (pintype "passive"))
      (node (ref "U40") (pin "N1") (pinfunction "VREF-_N1") (pintype "passive"))
      (node (ref "U45") (pin "2") (pinfunction "GND_2") (pintype "passive"))
      (node (ref "X1") (pin "2") (pinfunction "GND_2") (pintype "passive"))
    )
    (net (code "38") (name "Net-(D3-K)") (class "Default")
      (node (ref "C63") (pin "2") (pinfunction "2_2") (pintype "passive"))
      (node (ref "C66") (pin "1") (pinfunction "1_1") (pintype "passive"))
      (node (ref "D3") (pin "2") (pinfunction "K_2") (pintype "passive"))
      (node (ref "D4") (pin "2") (pinfunction "K_2") (pintype "passive"))
      (node (ref "D5") (pin "2") (pinfunction "K_2") (pintype "passive"))
      (node (ref "D6") (pin "2") (pinfunction "K_2") (pintype "passive"))
      (node (ref "U27") (pin "1") (pinfunction "Vin_1") (pintype "passive"))
      (node (ref "U27") (pin "3") (pinfunction "CE_3") (pintype "passive"))
    )
    (net (code "39") (name "Net-(LD7-Pad1)") (class "Default")
      (node (ref "LD7") (pin "1") (pintype "passive"))
      (node (ref "R221") (pin "2") (pinfunction "2_2") (pintype "passive"))
    )
    (net (code "40") (name "Net-(LD8-Red_anode)") (class "Default")
      (node (ref "LD8") (pin "2") (pinfunction "Red_anode_2") (pintype "passive"))
      (node (ref "R296") (pin "1") (pinfunction "1_1") (pintype "passive"))
    )
    (net (code "41") (name "Net-(LD8-YellowGreen_cathode)") (class "Default")
      (node (ref "LD8") (pin "3") (pinfunction "YellowGreen_cathode_3") (pintype "passive"))
      (node (ref "R295") (pin "1") (pinfunction "1_1") (pintype "passive"))
    )
    (net (code "42") (name "Net-(U25-OUT)") (class "Default")
      (node (ref "C72") (pin "2") (pinfunction "2_2") (pintype "passive"))
      (node (ref "SB41") (pin "1") (pinfunction "1_1") (pintype "passive"))
      (node (ref "U25") (pin "1") (pinfunction "OUT_1") (pintype "passive"))
    )
    (net (code "43") (name "Net-(U25-~{FAULT})") (class "Default")
      (node (ref "LD7") (pin "2") (pintype "passive"))
      (node (ref "R215") (pin "2") (pinfunction "2_2") (pintype "passive"))
      (node (ref "U25") (pin "3") (pinfunction "~{FAULT}_3") (pintype "passive"))
    )
    (net (code "44") (name "Net-(U27-BYPASS)") (class "Default")
      (node (ref "C71") (pin "2") (pinfunction "2_2") (pintype "passive"))
      (node (ref "U27") (pin "4") (pinfunction "BYPASS_4") (pintype "passive"))
    )
    (net (code "45") (name "Net-(U40A-BOOT0)") (class "Default")
      (node (ref "R280") (pin "2") (pinfunction "2_2") (pintype "passive"))
      (node (ref "U40") (pin "D6") (pinfunction "BOOT0_D6") (pintype "passive"))
    )
    (net (code "46") (name "Net-(U40A-NRST)") (class "Default")
      (node (ref "C141") (pin "2") (pinfunction "2_2") (pintype "passive"))
      (node (ref "CN30") (pin "2") (pinfunction "2_2") (pintype "passive"))
      (node (ref "U40") (pin "J1") (pinfunction "NRST_J1") (pintype "passive"))
    )
    (net (code "47") (name "Net-(U40A-OSC_IN{slash}PH0)") (class "Default")
      (node (ref "R284") (pin "2") (pinfunction "2_2") (pintype "passive"))
      (node (ref "U40") (pin "G1") (pinfunction "OSC_IN/PH0_G1") (pintype "passive"))
    )
    (net (code "48") (name "Net-(U40A-PDR_ON)") (class "Default")
      (node (ref "R278") (pin "2") (pinfunction "2_2") (pintype "passive"))
      (node (ref "U40") (pin "C6") (pinfunction "PDR_ON_C6") (pintype "passive"))
    )
    (net (code "49") (name "Net-(U40A-REXT_OTGPHY)") (class "Default")
      (node (ref "R269") (pin "2") (pinfunction "2_2") (pintype "passive"))
      (node (ref "U40") (pin "J15") (pinfunction "REXT_OTGPHY_J15") (pintype "passive"))
    )
    (net (code "50") (name "Net-(U40A-T_VCC_AIN{slash}PA0)") (class "Default")
      (node (ref "R281") (pin "1") (pinfunction "1_1") (pintype "passive"))
      (node (ref "R282") (pin "1") (pinfunction "1_1") (pintype "passive"))
      (node (ref "U40") (pin "N3") (pinfunction "T_VCC_AIN/PA0_N3") (pintype "passive"))
    )
    (net (code "51") (name "Net-(U40A-V12_OTGPHY)") (class "Default")
      (node (ref "C114") (pin "2") (pinfunction "2_2") (pintype "passive"))
      (node (ref "U40") (pin "J14") (pinfunction "V12_OTGPHY_J14") (pintype "passive"))
    )
    (net (code "52") (name "Net-(U40B-BYPASS-REG)") (class "Default")
      (node (ref "R283") (pin "2") (pinfunction "2_2") (pintype "passive"))
      (node (ref "U40") (pin "L4") (pinfunction "BYPASS-REG_L4") (pintype "passive"))
    )
    (net (code "53") (name "Net-(U40B-VCAP1)") (class "Default")
      (node (ref "C122") (pin "2") (pinfunction "2_2") (pintype "passive"))
      (node (ref "U40") (pin "M10") (pinfunction "VCAP1_M10") (pintype "passive"))
    )
    (net (code "54") (name "Net-(U40B-VCAP2)") (class "Default")
      (node (ref "C115") (pin "2") (pinfunction "2_2") (pintype "passive"))
      (node (ref "U40") (pin "F13") (pinfunction "VCAP2_F13") (pintype "passive"))
    )
    (net (code "55") (name "Net-(X1-EN)") (class "Default")
      (node (ref "R288") (pin "2") (pinfunction "2_2") (pintype "passive"))
      (node (ref "X1") (pin "1") (pinfunction "EN_1") (pintype "passive"))
    )
    (net (code "56") (name "Net-(X1-OUT)") (class "Default")
      (node (ref "R284") (pin "1") (pinfunction "1_1") (pintype "passive"))
      (node (ref "X1") (pin "3") (pinfunction "OUT_3") (pintype "passive"))
    )
    (net (code "57") (name "VDD") (class "Default")
      (node (ref "CN16") (pin "3") (pinfunction "3_3") (pintype "passive"))
      (node (ref "R282") (pin "2") (pinfunction "2_2") (pintype "passive"))
    )
    (net (code "58") (name "unconnected-(CN16-Pad1)") (class "Default")
      (node (ref "CN16") (pin "1") (pinfunction "1_1") (pintype "passive+no_connect"))
    )
    (net (code "59") (name "unconnected-(CN16-Pad2)") (class "Default")
      (node (ref "CN16") (pin "2") (pinfunction "2_2") (pintype "passive+no_connect"))
    )
    (net (code "60") (name "unconnected-(CN16-Pad9)") (class "Default")
      (node (ref "CN16") (pin "9") (pinfunction "9_9") (pintype "passive+no_connect"))
    )
    (net (code "61") (name "unconnected-(CN21-ID-Pad4)") (class "Default")
      (node (ref "CN21") (pin "4") (pinfunction "ID_4") (pintype "passive+no_connect"))
    )
    (net (code "62") (name "unconnected-(U31-NC-Pad4)") (class "Default")
      (node (ref "U31") (pin "4") (pinfunction "NC_4") (pintype "passive+no_connect"))
    )
    (net (code "63") (name "unconnected-(U40A-HW_TYP_0{slash}PI4-PadD4)") (class "Default")
      (node (ref "U40") (pin "D4") (pinfunction "HW_TYP_0/PI4_D4") (pintype "passive+no_connect"))
    )
    (net (code "64") (name "unconnected-(U40A-HW_TYP_1{slash}PI5-PadC4)") (class "Default")
      (node (ref "U40") (pin "C4") (pinfunction "HW_TYP_1/PI5_C4") (pintype "passive+no_connect"))
    )
    (net (code "65") (name "unconnected-(U40A-OSC_OUT{slash}PH1-PadH1)") (class "Default")
      (node (ref "U40") (pin "H1") (pinfunction "OSC_OUT/PH1_H1") (pintype "passive+no_connect"))
    )
    (net (code "66") (name "unconnected-(U40A-T_SW_DIR{slash}PA7-PadR3)") (class "Default")
      (node (ref "U40") (pin "R3") (pinfunction "T_SW_DIR/PA7_R3") (pintype "passive+no_connect"))
    )
    (net (code "67") (name "unconnected-(U45-IO3-Pad4)") (class "Default")
      (node (ref "U45") (pin "4") (pinfunction "IO3_4") (pintype "passive+no_connect"))
    )
    (net (code "68") (name "unconnected-(U45-IO4-Pad5)") (class "Default")
      (node (ref "U45") (pin "5") (pinfunction "IO4_5") (pintype "passive+no_connect"))
    )
  )
)
